# G785E.net
KiCad netlist of a schematic drawn in EAGLE
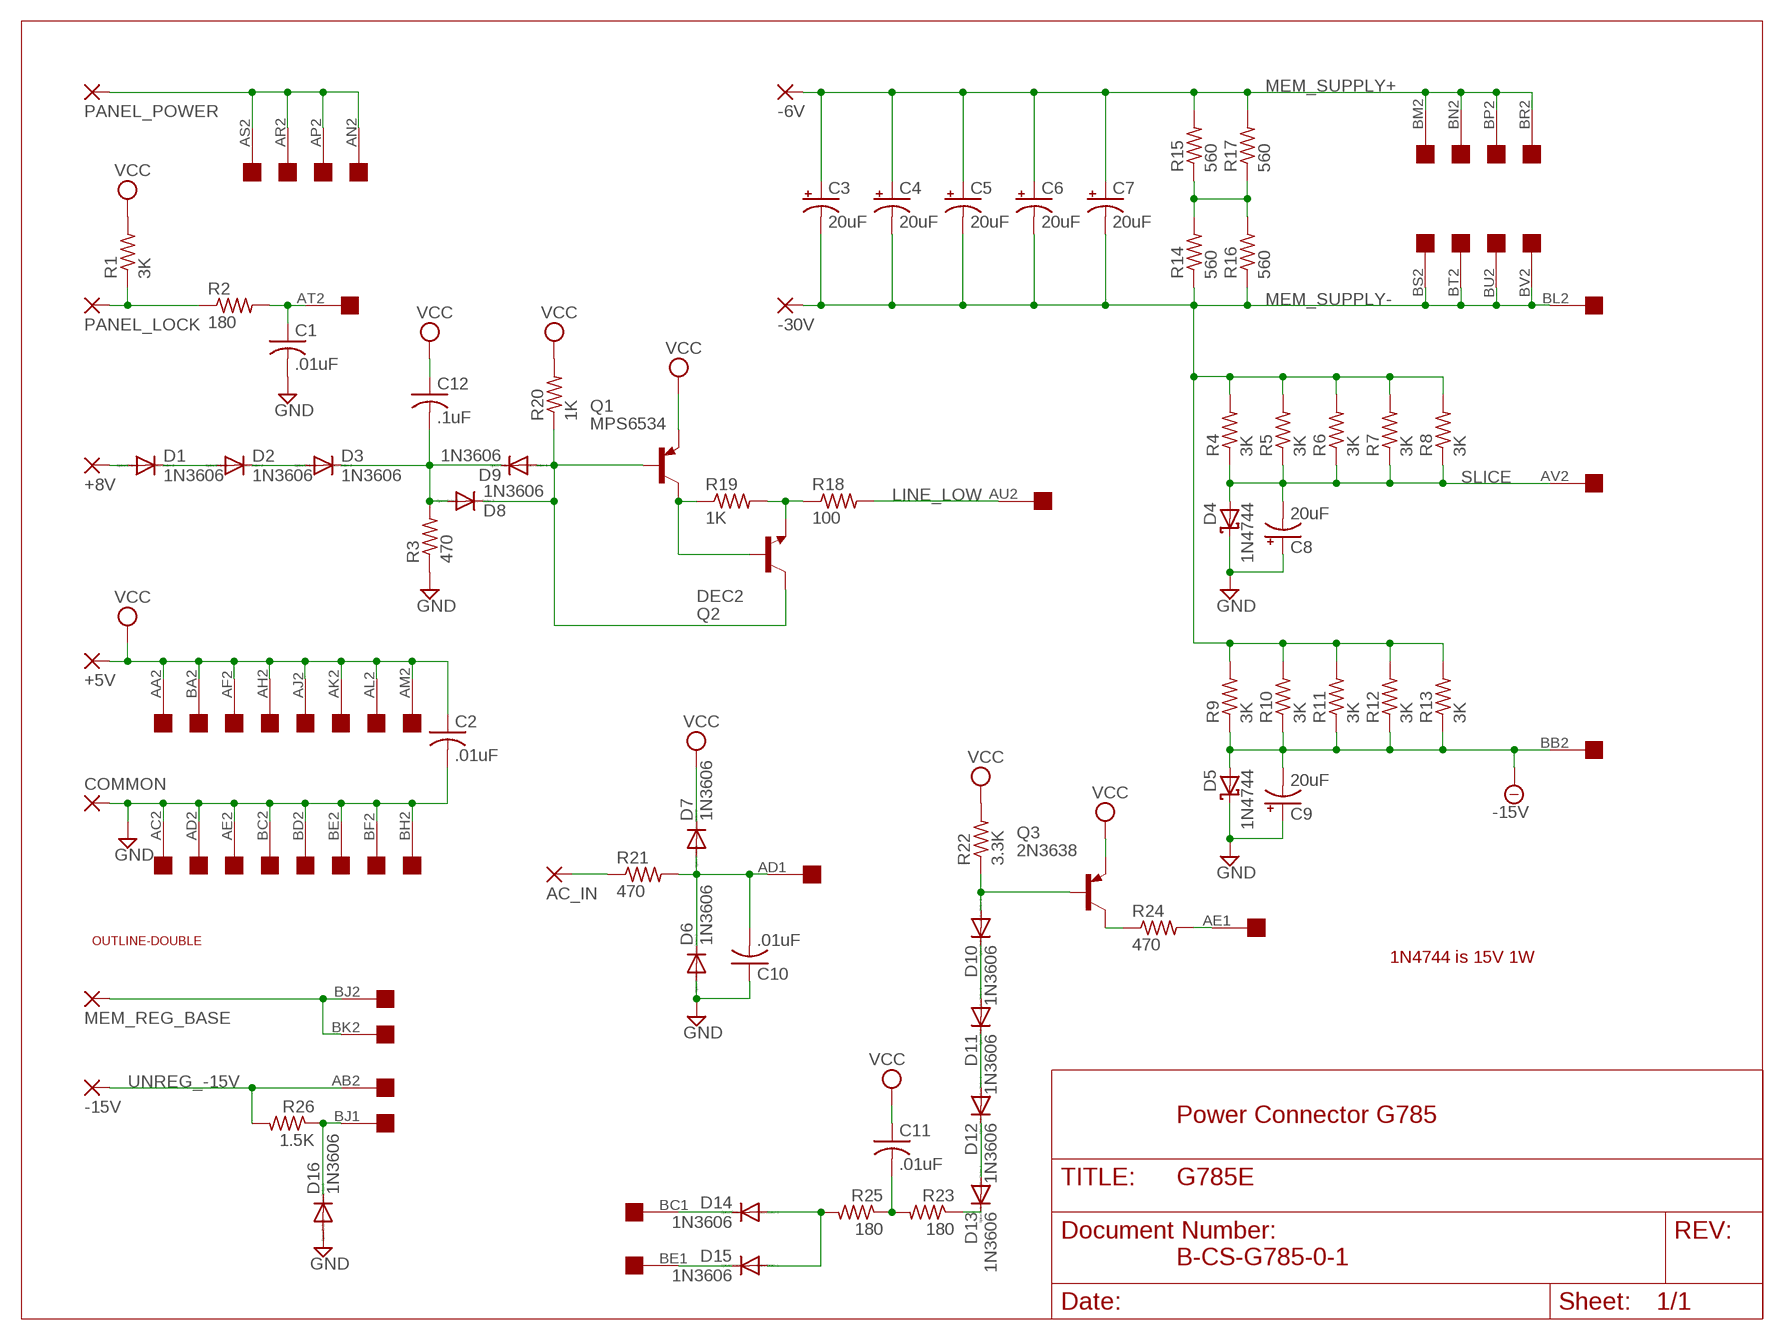
[diagram p0: schematic, sheet 1]

(export (version "E")
  (design (tool "Eeschema 10.0.6"))
  (components
    (comp (ref "+5V")
      (value "3,81/1,4")
      (footprint "eagle-import:3,81_1,4")
      (libsource (lib "eagle-import") (part "3,81/1,4"))
    )
    (comp (ref "+8V")
      (value "3,81/1,4")
      (footprint "eagle-import:3,81_1,4")
      (libsource (lib "eagle-import") (part "3,81/1,4"))
    )
    (comp (ref "-6V")
      (value "3,81/1,4")
      (footprint "eagle-import:3,81_1,4")
      (libsource (lib "eagle-import") (part "3,81/1,4"))
    )
    (comp (ref "-15V")
      (value "3,81/1,4")
      (footprint "eagle-import:3,81_1,4")
      (libsource (lib "eagle-import") (part "3,81/1,4"))
    )
    (comp (ref "-30V")
      (value "3,81/1,4")
      (footprint "eagle-import:3,81_1,4")
      (libsource (lib "eagle-import") (part "3,81/1,4"))
    )
    (comp (ref "AC_IN")
      (value "3,81/1,4")
      (footprint "eagle-import:3,81_1,4")
      (libsource (lib "eagle-import") (part "3,81/1,4"))
    )
    (comp (ref "C1")
      (value ".01uF")
      (footprint "eagle-import:C050-025X075")
      (libsource (lib "eagle-import") (part "C-US050-025X075"))
    )
    (comp (ref "C2")
      (value ".01uF")
      (footprint "eagle-import:C050-025X075")
      (libsource (lib "eagle-import") (part "C-US050-025X075"))
    )
    (comp (ref "C3")
      (value "20uF")
      (footprint "eagle-import:E25-9")
      (libsource (lib "eagle-import") (part "CPOL-USE25-9AXIAL"))
    )
    (comp (ref "C4")
      (value "20uF")
      (footprint "eagle-import:E25-9")
      (libsource (lib "eagle-import") (part "CPOL-USE25-9AXIAL"))
    )
    (comp (ref "C5")
      (value "20uF")
      (footprint "eagle-import:E25-9")
      (libsource (lib "eagle-import") (part "CPOL-USE25-9AXIAL"))
    )
    (comp (ref "C6")
      (value "20uF")
      (footprint "eagle-import:E25-9")
      (libsource (lib "eagle-import") (part "CPOL-USE25-9AXIAL"))
    )
    (comp (ref "C7")
      (value "20uF")
      (footprint "eagle-import:E25-9")
      (libsource (lib "eagle-import") (part "CPOL-USE25-9AXIAL"))
    )
    (comp (ref "C8")
      (value "20uF")
      (footprint "eagle-import:E25-9")
      (libsource (lib "eagle-import") (part "CPOL-USE25-9AXIAL"))
    )
    (comp (ref "C9")
      (value "20uF")
      (footprint "eagle-import:E25-9")
      (libsource (lib "eagle-import") (part "CPOL-USE25-9AXIAL"))
    )
    (comp (ref "C10")
      (value ".01uF")
      (footprint "eagle-import:C050-025X075")
      (libsource (lib "eagle-import") (part "C-US050-025X075"))
    )
    (comp (ref "C11")
      (value ".01uF")
      (footprint "eagle-import:C050-025X075")
      (libsource (lib "eagle-import") (part "C-US050-025X075"))
    )
    (comp (ref "C12")
      (value ".1uF")
      (footprint "eagle-import:C102-043X133")
      (libsource (lib "eagle-import") (part "C-US102-043X133"))
    )
    (comp (ref "COMMON")
      (value "3,81/1,4")
      (footprint "eagle-import:3,81_1,4")
      (libsource (lib "eagle-import") (part "3,81/1,4"))
    )
    (comp (ref "D1")
      (value "1N3606")
      (footprint "eagle-import:DO35-10")
      (libsource (lib "eagle-import") (part "1N4148DO35-10"))
    )
    (comp (ref "D2")
      (value "1N3606")
      (footprint "eagle-import:DO35-10")
      (libsource (lib "eagle-import") (part "1N4148DO35-10"))
    )
    (comp (ref "D3")
      (value "1N3606")
      (footprint "eagle-import:DO35-10")
      (libsource (lib "eagle-import") (part "1N4148DO35-10"))
    )
    (comp (ref "D4")
      (value "1N4744")
      (footprint "eagle-import:DO35-10")
      (libsource (lib "eagle-import") (part "BAT42"))
    )
    (comp (ref "D5")
      (value "1N4744")
      (footprint "eagle-import:DO35-10")
      (libsource (lib "eagle-import") (part "BAT42"))
    )
    (comp (ref "D6")
      (value "1N3606")
      (footprint "eagle-import:DO35-10")
      (libsource (lib "eagle-import") (part "1N4148DO35-10"))
    )
    (comp (ref "D7")
      (value "1N3606")
      (footprint "eagle-import:DO35-10")
      (libsource (lib "eagle-import") (part "1N4148DO35-10"))
    )
    (comp (ref "D8")
      (value "1N3606")
      (footprint "eagle-import:DO35-10")
      (libsource (lib "eagle-import") (part "1N4148DO35-10"))
    )
    (comp (ref "D9")
      (value "1N3606")
      (footprint "eagle-import:DO35-10")
      (libsource (lib "eagle-import") (part "1N4148DO35-10"))
    )
    (comp (ref "D10")
      (value "1N3606")
      (footprint "eagle-import:DO35-10")
      (libsource (lib "eagle-import") (part "1N4148DO35-10"))
    )
    (comp (ref "D11")
      (value "1N3606")
      (footprint "eagle-import:DO35-10")
      (libsource (lib "eagle-import") (part "1N4148DO35-10"))
    )
    (comp (ref "D12")
      (value "1N3606")
      (footprint "eagle-import:DO35-10")
      (libsource (lib "eagle-import") (part "1N4148DO35-10"))
    )
    (comp (ref "D13")
      (value "1N3606")
      (footprint "eagle-import:DO35-10")
      (libsource (lib "eagle-import") (part "1N4148DO35-10"))
    )
    (comp (ref "D14")
      (value "1N3606")
      (footprint "eagle-import:DO35-10")
      (libsource (lib "eagle-import") (part "1N4148DO35-10"))
    )
    (comp (ref "D15")
      (value "1N3606")
      (footprint "eagle-import:DO35-10")
      (libsource (lib "eagle-import") (part "1N4148DO35-10"))
    )
    (comp (ref "D16")
      (value "1N3606")
      (footprint "eagle-import:DO35-10")
      (libsource (lib "eagle-import") (part "1N4148DO35-10"))
    )
    (comp (ref "MEM_REG_BASE")
      (value "3,81/1,4")
      (footprint "eagle-import:3,81_1,4")
      (libsource (lib "eagle-import") (part "3,81/1,4"))
    )
    (comp (ref "PANEL_LOCK")
      (value "3,81/1,4")
      (footprint "eagle-import:3,81_1,4")
      (libsource (lib "eagle-import") (part "3,81/1,4"))
    )
    (comp (ref "PANEL_POWER")
      (value "3,81/1,4")
      (footprint "eagle-import:3,81_1,4")
      (libsource (lib "eagle-import") (part "3,81/1,4"))
    )
    (comp (ref "Q1")
      (value "MPS6534")
      (footprint "eagle-import:TO39")
      (libsource (lib "eagle-import") (part "2N2904"))
    )
    (comp (ref "Q2")
      (value "DEC2")
      (footprint "eagle-import:TO5")
      (libsource (lib "eagle-import") (part "2N2219"))
    )
    (comp (ref "Q3")
      (value "2N3638")
      (footprint "eagle-import:TO39")
      (libsource (lib "eagle-import") (part "2N2904"))
    )
    (comp (ref "R1")
      (value "3K")
      (footprint "eagle-import:0207_10")
      (libsource (lib "eagle-import") (part "R-US_0207/10"))
    )
    (comp (ref "R2")
      (value "180")
      (footprint "eagle-import:0207_10")
      (libsource (lib "eagle-import") (part "R-US_0207/10"))
    )
    (comp (ref "R3")
      (value "470")
      (footprint "eagle-import:0207_10")
      (libsource (lib "eagle-import") (part "R-US_0207/10"))
    )
    (comp (ref "R4")
      (value "3K")
      (footprint "eagle-import:0207_10")
      (libsource (lib "eagle-import") (part "R-US_0207/10"))
    )
    (comp (ref "R5")
      (value "3K")
      (footprint "eagle-import:0207_10")
      (libsource (lib "eagle-import") (part "R-US_0207/10"))
    )
    (comp (ref "R6")
      (value "3K")
      (footprint "eagle-import:0207_10")
      (libsource (lib "eagle-import") (part "R-US_0207/10"))
    )
    (comp (ref "R7")
      (value "3K")
      (footprint "eagle-import:0207_10")
      (libsource (lib "eagle-import") (part "R-US_0207/10"))
    )
    (comp (ref "R8")
      (value "3K")
      (footprint "eagle-import:0207_10")
      (libsource (lib "eagle-import") (part "R-US_0207/10"))
    )
    (comp (ref "R9")
      (value "3K")
      (footprint "eagle-import:0207_10")
      (libsource (lib "eagle-import") (part "R-US_0207/10"))
    )
    (comp (ref "R10")
      (value "3K")
      (footprint "eagle-import:0207_10")
      (libsource (lib "eagle-import") (part "R-US_0207/10"))
    )
    (comp (ref "R11")
      (value "3K")
      (footprint "eagle-import:0207_10")
      (libsource (lib "eagle-import") (part "R-US_0207/10"))
    )
    (comp (ref "R12")
      (value "3K")
      (footprint "eagle-import:0207_10")
      (libsource (lib "eagle-import") (part "R-US_0207/10"))
    )
    (comp (ref "R13")
      (value "3K")
      (footprint "eagle-import:0207_10")
      (libsource (lib "eagle-import") (part "R-US_0207/10"))
    )
    (comp (ref "R14")
      (value "560")
      (footprint "eagle-import:0207_10")
      (libsource (lib "eagle-import") (part "R-US_0207/10"))
    )
    (comp (ref "R15")
      (value "560")
      (footprint "eagle-import:0207_10")
      (libsource (lib "eagle-import") (part "R-US_0207/10"))
    )
    (comp (ref "R16")
      (value "560")
      (footprint "eagle-import:0207_10")
      (libsource (lib "eagle-import") (part "R-US_0207/10"))
    )
    (comp (ref "R17")
      (value "560")
      (footprint "eagle-import:0207_10")
      (libsource (lib "eagle-import") (part "R-US_0207/10"))
    )
    (comp (ref "R18")
      (value "100")
      (footprint "eagle-import:0207_10")
      (libsource (lib "eagle-import") (part "R-US_0207/10"))
    )
    (comp (ref "R19")
      (value "1K")
      (footprint "eagle-import:0207_10")
      (libsource (lib "eagle-import") (part "R-US_0207/10"))
    )
    (comp (ref "R20")
      (value "1K")
      (footprint "eagle-import:0207_10")
      (libsource (lib "eagle-import") (part "R-US_0207/10"))
    )
    (comp (ref "R21")
      (value "470")
      (footprint "eagle-import:0207_10")
      (libsource (lib "eagle-import") (part "R-US_0207/10"))
    )
    (comp (ref "R22")
      (value "3.3K")
      (footprint "eagle-import:0207_10")
      (libsource (lib "eagle-import") (part "R-US_0207/10"))
    )
    (comp (ref "R23")
      (value "180")
      (footprint "eagle-import:0207_10")
      (libsource (lib "eagle-import") (part "R-US_0207/10"))
    )
    (comp (ref "R24")
      (value "470")
      (footprint "eagle-import:0207_10")
      (libsource (lib "eagle-import") (part "R-US_0207/10"))
    )
    (comp (ref "R25")
      (value "180")
      (footprint "eagle-import:0207_10")
      (libsource (lib "eagle-import") (part "R-US_0207/10"))
    )
    (comp (ref "R26")
      (value "1.5K")
      (footprint "eagle-import:0207_10")
      (libsource (lib "eagle-import") (part "R-US_0207/10"))
    )
    (comp (ref "U$1")
      (value "DOUBLE")
      (footprint "eagle-import:EDGE-CON4")
      (libsource (lib "eagle-import") (part "DOUBLE"))
    )
    (comp (ref "U$2")
      (value "OUTLINE-DOUBLE")
      (footprint "eagle-import:DOUBLE")
      (libsource (lib "eagle-import") (part "OUTLINE-DOUBLE"))
    )
  )
  (nets
    (net (code "1") (name "-15V") (class "Default")
      (node (ref "C9") (pin "-") (pinfunction "-_-") (pintype "passive"))
      (node (ref "D5") (pin "A") (pinfunction "A_A") (pintype "passive"))
      (node (ref "R10") (pin "1") (pinfunction "1_1") (pintype "passive"))
      (node (ref "R11") (pin "1") (pinfunction "1_1") (pintype "passive"))
      (node (ref "R12") (pin "1") (pinfunction "1_1") (pintype "passive"))
      (node (ref "R13") (pin "1") (pinfunction "1_1") (pintype "passive"))
      (node (ref "R9") (pin "1") (pinfunction "1_1") (pintype "passive"))
      (node (ref "U$1") (pin "BB2") (pinfunction "1_BB2") (pintype "bidirectional"))
    )
    (net (code "2") (name "/LINE_LOW") (class "Default")
      (node (ref "R18") (pin "2") (pinfunction "2_2") (pintype "passive"))
      (node (ref "U$1") (pin "AU2") (pinfunction "1_AU2") (pintype "bidirectional"))
    )
    (net (code "3") (name "/MEM_SUPPLY+") (class "Default")
      (node (ref "-6V") (pin "1") (pinfunction "P_1") (pintype "passive"))
      (node (ref "C3") (pin "+") (pinfunction "+_+") (pintype "passive"))
      (node (ref "C4") (pin "+") (pinfunction "+_+") (pintype "passive"))
      (node (ref "C5") (pin "+") (pinfunction "+_+") (pintype "passive"))
      (node (ref "C6") (pin "+") (pinfunction "+_+") (pintype "passive"))
      (node (ref "C7") (pin "+") (pinfunction "+_+") (pintype "passive"))
      (node (ref "R15") (pin "2") (pinfunction "2_2") (pintype "passive"))
      (node (ref "R17") (pin "2") (pinfunction "2_2") (pintype "passive"))
      (node (ref "U$1") (pin "BM2") (pinfunction "1_BM2") (pintype "bidirectional"))
      (node (ref "U$1") (pin "BN2") (pinfunction "1_BN2") (pintype "bidirectional"))
      (node (ref "U$1") (pin "BP2") (pinfunction "1_BP2") (pintype "bidirectional"))
      (node (ref "U$1") (pin "BR2") (pinfunction "1_BR2") (pintype "bidirectional"))
    )
    (net (code "4") (name "/MEM_SUPPLY-") (class "Default")
      (node (ref "-30V") (pin "1") (pinfunction "P_1") (pintype "passive"))
      (node (ref "C3") (pin "-") (pinfunction "-_-") (pintype "passive"))
      (node (ref "C4") (pin "-") (pinfunction "-_-") (pintype "passive"))
      (node (ref "C5") (pin "-") (pinfunction "-_-") (pintype "passive"))
      (node (ref "C6") (pin "-") (pinfunction "-_-") (pintype "passive"))
      (node (ref "C7") (pin "-") (pinfunction "-_-") (pintype "passive"))
      (node (ref "R10") (pin "2") (pinfunction "2_2") (pintype "passive"))
      (node (ref "R11") (pin "2") (pinfunction "2_2") (pintype "passive"))
      (node (ref "R12") (pin "2") (pinfunction "2_2") (pintype "passive"))
      (node (ref "R13") (pin "2") (pinfunction "2_2") (pintype "passive"))
      (node (ref "R14") (pin "1") (pinfunction "1_1") (pintype "passive"))
      (node (ref "R16") (pin "1") (pinfunction "1_1") (pintype "passive"))
      (node (ref "R4") (pin "2") (pinfunction "2_2") (pintype "passive"))
      (node (ref "R5") (pin "2") (pinfunction "2_2") (pintype "passive"))
      (node (ref "R6") (pin "2") (pinfunction "2_2") (pintype "passive"))
      (node (ref "R7") (pin "2") (pinfunction "2_2") (pintype "passive"))
      (node (ref "R8") (pin "2") (pinfunction "2_2") (pintype "passive"))
      (node (ref "R9") (pin "2") (pinfunction "2_2") (pintype "passive"))
      (node (ref "U$1") (pin "BL2") (pinfunction "1_BL2") (pintype "bidirectional"))
      (node (ref "U$1") (pin "BS2") (pinfunction "1_BS2") (pintype "bidirectional"))
      (node (ref "U$1") (pin "BT2") (pinfunction "1_BT2") (pintype "bidirectional"))
      (node (ref "U$1") (pin "BU2") (pinfunction "1_BU2") (pintype "bidirectional"))
      (node (ref "U$1") (pin "BV2") (pinfunction "1_BV2") (pintype "bidirectional"))
    )
    (net (code "5") (name "/SLICE") (class "Default")
      (node (ref "C8") (pin "-") (pinfunction "-_-") (pintype "passive"))
      (node (ref "D4") (pin "A") (pinfunction "A_A") (pintype "passive"))
      (node (ref "R4") (pin "1") (pinfunction "1_1") (pintype "passive"))
      (node (ref "R5") (pin "1") (pinfunction "1_1") (pintype "passive"))
      (node (ref "R6") (pin "1") (pinfunction "1_1") (pintype "passive"))
      (node (ref "R7") (pin "1") (pinfunction "1_1") (pintype "passive"))
      (node (ref "R8") (pin "1") (pinfunction "1_1") (pintype "passive"))
      (node (ref "U$1") (pin "AV2") (pinfunction "1_AV2") (pintype "bidirectional"))
    )
    (net (code "6") (name "/UNREG_-15V") (class "Default")
      (node (ref "-15V") (pin "1") (pinfunction "P_1") (pintype "passive"))
      (node (ref "R26") (pin "2") (pinfunction "2_2") (pintype "passive"))
      (node (ref "U$1") (pin "AB2") (pinfunction "1_AB2") (pintype "bidirectional"))
    )
    (net (code "7") (name "GND") (class "Default")
      (node (ref "C1") (pin "2") (pinfunction "2_2") (pintype "passive"))
      (node (ref "C10") (pin "1") (pinfunction "1_1") (pintype "passive"))
      (node (ref "C2") (pin "2") (pinfunction "2_2") (pintype "passive"))
      (node (ref "C8") (pin "+") (pinfunction "+_+") (pintype "passive"))
      (node (ref "C9") (pin "+") (pinfunction "+_+") (pintype "passive"))
      (node (ref "COMMON") (pin "1") (pinfunction "P_1") (pintype "passive"))
      (node (ref "D16") (pin "A") (pinfunction "A_A") (pintype "passive"))
      (node (ref "D4") (pin "C") (pinfunction "C_C") (pintype "passive"))
      (node (ref "D5") (pin "C") (pinfunction "C_C") (pintype "passive"))
      (node (ref "D6") (pin "A") (pinfunction "A_A") (pintype "passive"))
      (node (ref "R3") (pin "1") (pinfunction "1_1") (pintype "passive"))
      (node (ref "U$1") (pin "AC2") (pinfunction "1_AC2") (pintype "bidirectional"))
      (node (ref "U$1") (pin "AD2") (pinfunction "1_AD2") (pintype "bidirectional"))
      (node (ref "U$1") (pin "AE2") (pinfunction "1_AE2") (pintype "bidirectional"))
      (node (ref "U$1") (pin "BC2") (pinfunction "1_BC2") (pintype "bidirectional"))
      (node (ref "U$1") (pin "BD2") (pinfunction "1_BD2") (pintype "bidirectional"))
      (node (ref "U$1") (pin "BE2") (pinfunction "1_BE2") (pintype "bidirectional"))
      (node (ref "U$1") (pin "BF2") (pinfunction "1_BF2") (pintype "bidirectional"))
      (node (ref "U$1") (pin "BH2") (pinfunction "1_BH2") (pintype "bidirectional"))
    )
    (net (code "8") (name "Net-(+8V-P)") (class "Default")
      (node (ref "+8V") (pin "1") (pinfunction "P_1") (pintype "passive"))
      (node (ref "D1") (pin "A") (pinfunction "A_A") (pintype "passive"))
    )
    (net (code "9") (name "Net-(AC_IN-P)") (class "Default")
      (node (ref "AC_IN") (pin "1") (pinfunction "P_1") (pintype "passive"))
      (node (ref "R21") (pin "1") (pinfunction "1_1") (pintype "passive"))
    )
    (net (code "10") (name "Net-(C11-Pad2)") (class "Default")
      (node (ref "C11") (pin "2") (pinfunction "2_2") (pintype "passive"))
      (node (ref "R23") (pin "2") (pinfunction "2_2") (pintype "passive"))
      (node (ref "R25") (pin "1") (pinfunction "1_1") (pintype "passive"))
    )
    (net (code "11") (name "Net-(C12-Pad2)") (class "Default")
      (node (ref "C12") (pin "2") (pinfunction "2_2") (pintype "passive"))
      (node (ref "D3") (pin "C") (pinfunction "C_C") (pintype "passive"))
      (node (ref "D8") (pin "A") (pinfunction "A_A") (pintype "passive"))
      (node (ref "D9") (pin "C") (pinfunction "C_C") (pintype "passive"))
      (node (ref "R3") (pin "2") (pinfunction "2_2") (pintype "passive"))
    )
    (net (code "12") (name "Net-(D1-PadC)") (class "Default")
      (node (ref "D1") (pin "C") (pinfunction "C_C") (pintype "passive"))
      (node (ref "D2") (pin "A") (pinfunction "A_A") (pintype "passive"))
    )
    (net (code "13") (name "Net-(D2-PadC)") (class "Default")
      (node (ref "D2") (pin "C") (pinfunction "C_C") (pintype "passive"))
      (node (ref "D3") (pin "A") (pinfunction "A_A") (pintype "passive"))
    )
    (net (code "14") (name "Net-(D10-PadC)") (class "Default")
      (node (ref "D10") (pin "C") (pinfunction "C_C") (pintype "passive"))
      (node (ref "D11") (pin "A") (pinfunction "A_A") (pintype "passive"))
    )
    (net (code "15") (name "Net-(D11-PadC)") (class "Default")
      (node (ref "D11") (pin "C") (pinfunction "C_C") (pintype "passive"))
      (node (ref "D12") (pin "A") (pinfunction "A_A") (pintype "passive"))
    )
    (net (code "16") (name "Net-(D12-PadC)") (class "Default")
      (node (ref "D12") (pin "C") (pinfunction "C_C") (pintype "passive"))
      (node (ref "D13") (pin "A") (pinfunction "A_A") (pintype "passive"))
    )
    (net (code "17") (name "Net-(D13-PadC)") (class "Default")
      (node (ref "D13") (pin "C") (pinfunction "C_C") (pintype "passive"))
      (node (ref "R23") (pin "1") (pinfunction "1_1") (pintype "passive"))
    )
    (net (code "18") (name "Net-(D14-PadA)") (class "Default")
      (node (ref "D14") (pin "A") (pinfunction "A_A") (pintype "passive"))
      (node (ref "D15") (pin "A") (pinfunction "A_A") (pintype "passive"))
      (node (ref "R25") (pin "2") (pinfunction "2_2") (pintype "passive"))
    )
    (net (code "19") (name "Net-(MEM_REG_BASE-P)") (class "Default")
      (node (ref "MEM_REG_BASE") (pin "1") (pinfunction "P_1") (pintype "passive"))
      (node (ref "U$1") (pin "BJ2") (pinfunction "1_BJ2") (pintype "bidirectional"))
      (node (ref "U$1") (pin "BK2") (pinfunction "1_BK2") (pintype "bidirectional"))
    )
    (net (code "20") (name "Net-(PANEL_LOCK-P)") (class "Default")
      (node (ref "PANEL_LOCK") (pin "1") (pinfunction "P_1") (pintype "passive"))
      (node (ref "R1") (pin "1") (pinfunction "1_1") (pintype "passive"))
      (node (ref "R2") (pin "1") (pinfunction "1_1") (pintype "passive"))
    )
    (net (code "21") (name "Net-(PANEL_POWER-P)") (class "Default")
      (node (ref "PANEL_POWER") (pin "1") (pinfunction "P_1") (pintype "passive"))
      (node (ref "U$1") (pin "AN2") (pinfunction "1_AN2") (pintype "bidirectional"))
      (node (ref "U$1") (pin "AP2") (pinfunction "1_AP2") (pintype "bidirectional"))
      (node (ref "U$1") (pin "AR2") (pinfunction "1_AR2") (pintype "bidirectional"))
      (node (ref "U$1") (pin "AS2") (pinfunction "1_AS2") (pintype "bidirectional"))
    )
    (net (code "22") (name "Net-(Q1-B)") (class "Default")
      (node (ref "D8") (pin "C") (pinfunction "C_C") (pintype "passive"))
      (node (ref "D9") (pin "A") (pinfunction "A_A") (pintype "passive"))
      (node (ref "Q1") (pin "2") (pinfunction "B_2") (pintype "passive"))
      (node (ref "Q2") (pin "3") (pinfunction "C_3") (pintype "passive"))
      (node (ref "R20") (pin "1") (pinfunction "1_1") (pintype "passive"))
    )
    (net (code "23") (name "Net-(Q1-C)") (class "Default")
      (node (ref "Q1") (pin "3") (pinfunction "C_3") (pintype "passive"))
      (node (ref "Q2") (pin "2") (pinfunction "B_2") (pintype "passive"))
      (node (ref "R19") (pin "1") (pinfunction "1_1") (pintype "passive"))
    )
    (net (code "24") (name "Net-(Q2-E)") (class "Default")
      (node (ref "Q2") (pin "1") (pinfunction "E_1") (pintype "passive"))
      (node (ref "R18") (pin "1") (pinfunction "1_1") (pintype "passive"))
      (node (ref "R19") (pin "2") (pinfunction "2_2") (pintype "passive"))
    )
    (net (code "25") (name "Net-(Q3-B)") (class "Default")
      (node (ref "D10") (pin "A") (pinfunction "A_A") (pintype "passive"))
      (node (ref "Q3") (pin "2") (pinfunction "B_2") (pintype "passive"))
      (node (ref "R22") (pin "1") (pinfunction "1_1") (pintype "passive"))
    )
    (net (code "26") (name "Net-(Q3-C)") (class "Default")
      (node (ref "Q3") (pin "3") (pinfunction "C_3") (pintype "passive"))
      (node (ref "R24") (pin "1") (pinfunction "1_1") (pintype "passive"))
    )
    (net (code "27") (name "Net-(R14-Pad2)") (class "Default")
      (node (ref "R14") (pin "2") (pinfunction "2_2") (pintype "passive"))
      (node (ref "R15") (pin "1") (pinfunction "1_1") (pintype "passive"))
      (node (ref "R16") (pin "2") (pinfunction "2_2") (pintype "passive"))
      (node (ref "R17") (pin "1") (pinfunction "1_1") (pintype "passive"))
    )
    (net (code "28") (name "Net-(U$1AF-1)") (class "Default")
      (node (ref "C1") (pin "1") (pinfunction "1_1") (pintype "passive"))
      (node (ref "R2") (pin "2") (pinfunction "2_2") (pintype "passive"))
      (node (ref "U$1") (pin "AT2") (pinfunction "1_AT2") (pintype "bidirectional"))
    )
    (net (code "29") (name "Net-(U$1AO-1)") (class "Default")
      (node (ref "D14") (pin "C") (pinfunction "C_C") (pintype "passive"))
      (node (ref "U$1") (pin "BC1") (pinfunction "1_BC1") (pintype "bidirectional"))
    )
    (net (code "30") (name "Net-(U$1AS-1)") (class "Default")
      (node (ref "D15") (pin "C") (pinfunction "C_C") (pintype "passive"))
      (node (ref "U$1") (pin "BE1") (pinfunction "1_BE1") (pintype "bidirectional"))
    )
    (net (code "31") (name "Net-(U$1AY-1)") (class "Default")
      (node (ref "D16") (pin "C") (pinfunction "C_C") (pintype "passive"))
      (node (ref "R26") (pin "1") (pinfunction "1_1") (pintype "passive"))
      (node (ref "U$1") (pin "BJ1") (pinfunction "1_BJ1") (pintype "bidirectional"))
    )
    (net (code "32") (name "Net-(U$1G-1)") (class "Default")
      (node (ref "C10") (pin "2") (pinfunction "2_2") (pintype "passive"))
      (node (ref "D6") (pin "C") (pinfunction "C_C") (pintype "passive"))
      (node (ref "D7") (pin "A") (pinfunction "A_A") (pintype "passive"))
      (node (ref "R21") (pin "2") (pinfunction "2_2") (pintype "passive"))
      (node (ref "U$1") (pin "AD1") (pinfunction "1_AD1") (pintype "bidirectional"))
    )
    (net (code "33") (name "Net-(U$1I-1)") (class "Default")
      (node (ref "R24") (pin "2") (pinfunction "2_2") (pintype "passive"))
      (node (ref "U$1") (pin "AE1") (pinfunction "1_AE1") (pintype "bidirectional"))
    )
    (net (code "34") (name "VCC") (class "Default")
      (node (ref "+5V") (pin "1") (pinfunction "P_1") (pintype "passive"))
      (node (ref "C11") (pin "1") (pinfunction "1_1") (pintype "passive"))
      (node (ref "C12") (pin "1") (pinfunction "1_1") (pintype "passive"))
      (node (ref "C2") (pin "1") (pinfunction "1_1") (pintype "passive"))
      (node (ref "D7") (pin "C") (pinfunction "C_C") (pintype "passive"))
      (node (ref "Q1") (pin "1") (pinfunction "E_1") (pintype "passive"))
      (node (ref "Q3") (pin "1") (pinfunction "E_1") (pintype "passive"))
      (node (ref "R1") (pin "2") (pinfunction "2_2") (pintype "passive"))
      (node (ref "R20") (pin "2") (pinfunction "2_2") (pintype "passive"))
      (node (ref "R22") (pin "2") (pinfunction "2_2") (pintype "passive"))
      (node (ref "U$1") (pin "AA2") (pinfunction "1_AA2") (pintype "bidirectional"))
      (node (ref "U$1") (pin "AF2") (pinfunction "1_AF2") (pintype "bidirectional"))
      (node (ref "U$1") (pin "AH2") (pinfunction "1_AH2") (pintype "bidirectional"))
      (node (ref "U$1") (pin "AJ2") (pinfunction "1_AJ2") (pintype "bidirectional"))
      (node (ref "U$1") (pin "AK2") (pinfunction "1_AK2") (pintype "bidirectional"))
      (node (ref "U$1") (pin "AL2") (pinfunction "1_AL2") (pintype "bidirectional"))
      (node (ref "U$1") (pin "AM2") (pinfunction "1_AM2") (pintype "bidirectional"))
      (node (ref "U$1") (pin "BA2") (pinfunction "1_BA2") (pintype "bidirectional"))
    )
  )
)
